# RP_ComputeModule3_rev_3_0_Mechanics.net
KiCad netlist of a schematic drawn in Altium Designer
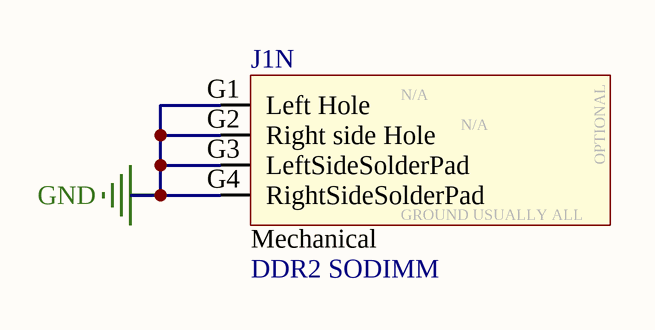
[diagram p0: RP_ComputeModule3_rev.3.0_Mechanics.SchDoc]

(export (version "E")
  (design (tool "Eeschema 10.0.6"))
  (components
    (comp (ref "J1")
      (value "DDR2 SODIMM")
      (footprint "TE 1473005-4 (DDR2 SO-DIMM)")
      (description "TE CONNECTIVITY / AMP         1473005-4             SOCKET IC, DIMM, DDR2, 1.8V, 200WAY")
      (fields
        (field (name "MANUFACTURER") "TE Connectivity")
        (field (name "MANUFACTURER PART NUMBER") "1473005-4")
      )
      (libsource (lib "TEConnectivity_AMP") (part "1473005-4"))
    )
  )
  (nets
    (net (code "1") (name "GND") (class "Default")
      (node (ref "J1") (pin "G1") (pinfunction "Left_Hole_G1") (pintype "passive"))
      (node (ref "J1") (pin "G2") (pinfunction "Right_side_Hole_G2") (pintype "passive"))
      (node (ref "J1") (pin "G3") (pinfunction "LeftSideSolderPad_G3") (pintype "power_in"))
      (node (ref "J1") (pin "G4") (pinfunction "RightSideSolderPad_G4") (pintype "power_in"))
    )
  )
)
